# controller.net
KiCad netlist of a schematic drawn in EAGLE
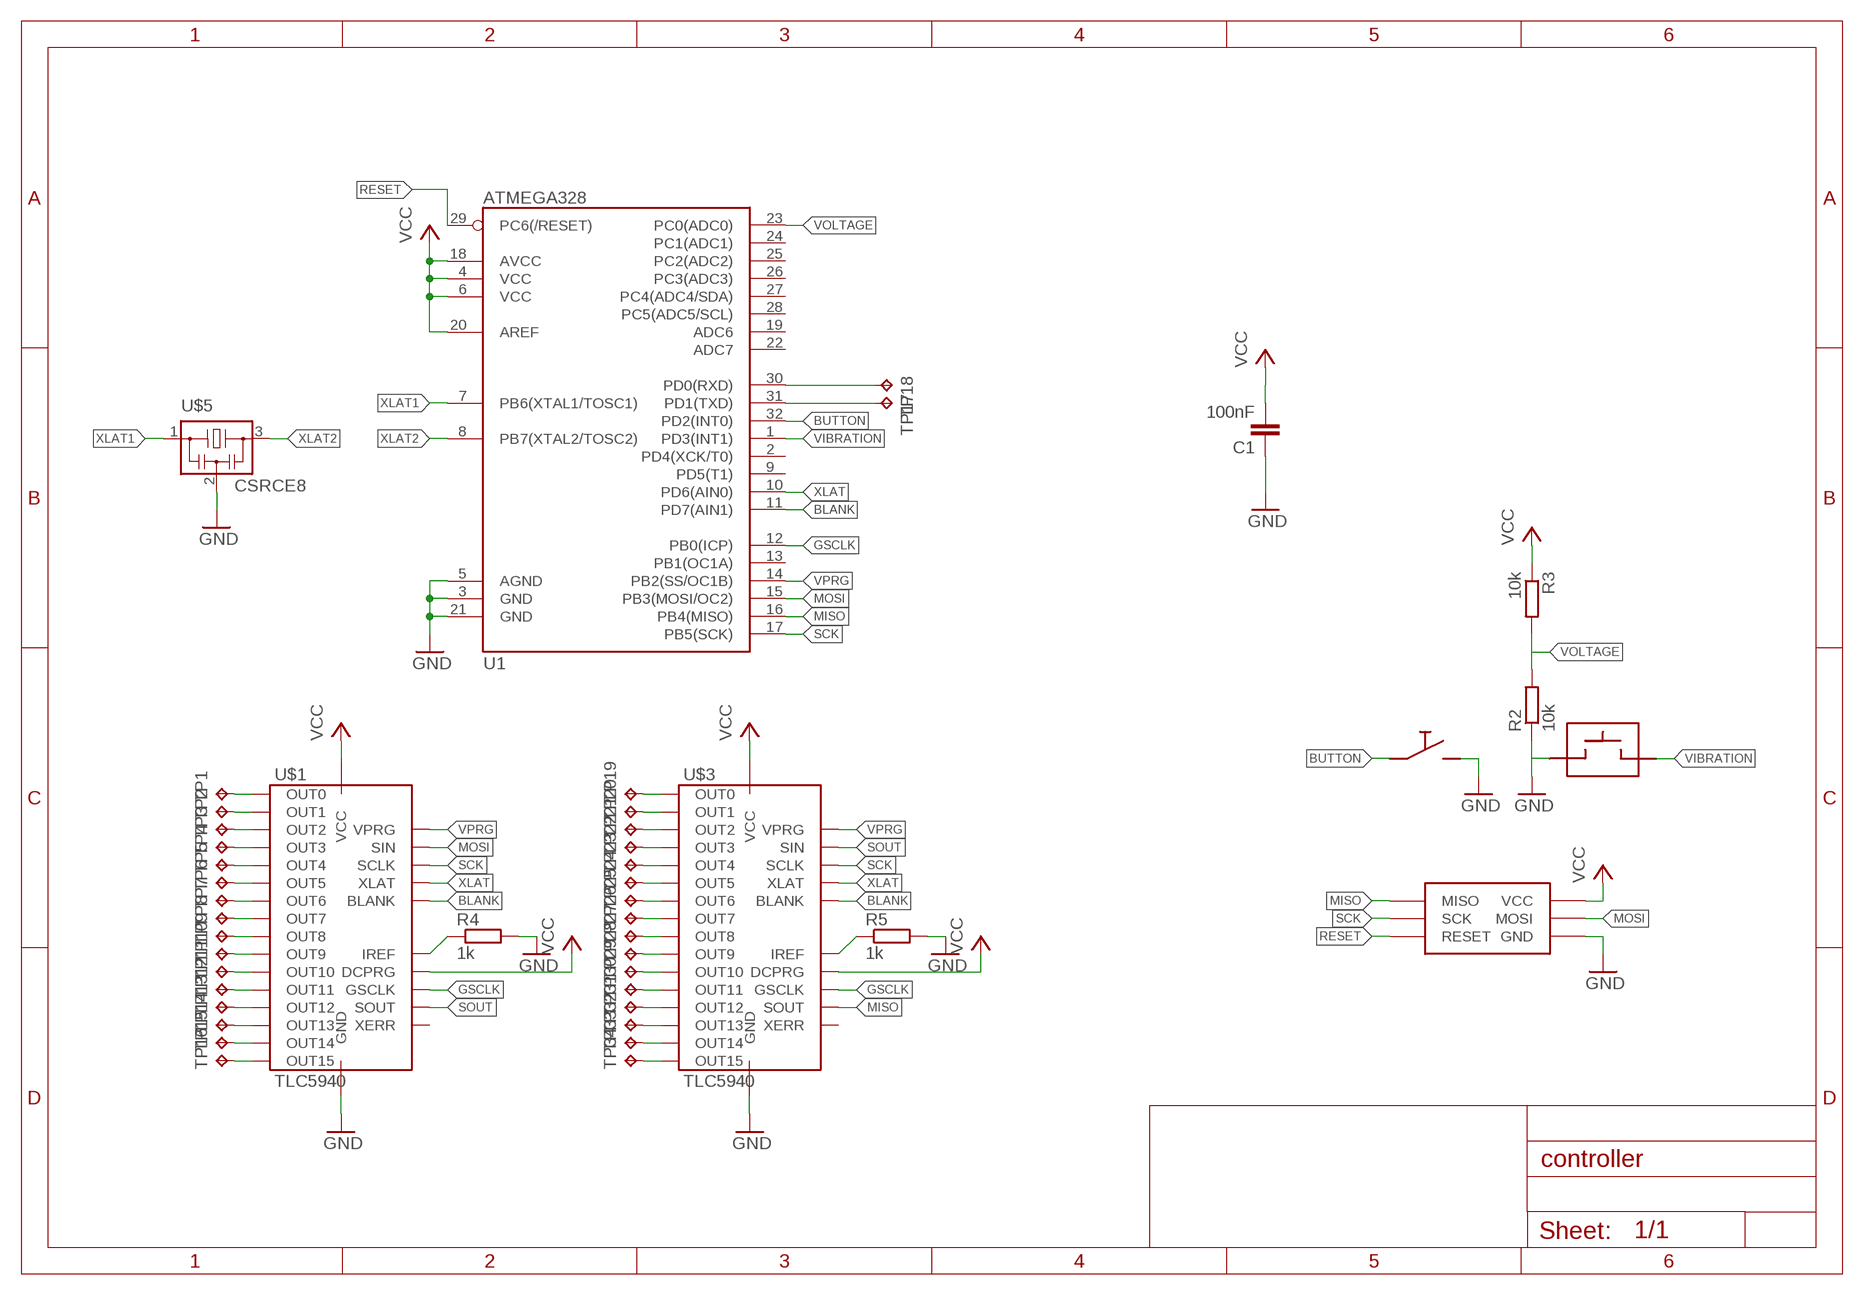
[diagram p0: schematic, sheet 1]

(export (version "E")
  (design (tool "Eeschema 10.0.6"))
  (components
    (comp (ref "C1")
      (value "100nF")
      (footprint "eagle-import:C0603")
      (libsource (lib "eagle-import") (part "C-EUC0603"))
    )
    (comp (ref "R2")
      (value "10k")
      (footprint "eagle-import:R0603")
      (libsource (lib "eagle-import") (part "R-EU_R0603"))
    )
    (comp (ref "R3")
      (value "10k")
      (footprint "eagle-import:R0603")
      (libsource (lib "eagle-import") (part "R-EU_R0603"))
    )
    (comp (ref "R4")
      (value "1k")
      (footprint "eagle-import:R0603")
      (libsource (lib "eagle-import") (part "R-EU_R0603"))
    )
    (comp (ref "R5")
      (value "1k")
      (footprint "eagle-import:R0603")
      (libsource (lib "eagle-import") (part "R-EU_R0603"))
    )
    (comp (ref "TP1")
      (value "TPTP15SQ")
      (footprint "eagle-import:TP15SQ")
      (libsource (lib "eagle-import") (part "TPTP15SQ"))
    )
    (comp (ref "TP2")
      (value "TPTP15SQ")
      (footprint "eagle-import:TP15SQ")
      (libsource (lib "eagle-import") (part "TPTP15SQ"))
    )
    (comp (ref "TP3")
      (value "TPTP15SQ")
      (footprint "eagle-import:TP15SQ")
      (libsource (lib "eagle-import") (part "TPTP15SQ"))
    )
    (comp (ref "TP4")
      (value "TPTP15SQ")
      (footprint "eagle-import:TP15SQ")
      (libsource (lib "eagle-import") (part "TPTP15SQ"))
    )
    (comp (ref "TP5")
      (value "TPTP15SQ")
      (footprint "eagle-import:TP15SQ")
      (libsource (lib "eagle-import") (part "TPTP15SQ"))
    )
    (comp (ref "TP6")
      (value "TPTP15SQ")
      (footprint "eagle-import:TP15SQ")
      (libsource (lib "eagle-import") (part "TPTP15SQ"))
    )
    (comp (ref "TP7")
      (value "TPTP15SQ")
      (footprint "eagle-import:TP15SQ")
      (libsource (lib "eagle-import") (part "TPTP15SQ"))
    )
    (comp (ref "TP8")
      (value "TPTP15SQ")
      (footprint "eagle-import:TP15SQ")
      (libsource (lib "eagle-import") (part "TPTP15SQ"))
    )
    (comp (ref "TP9")
      (value "TPTP15SQ")
      (footprint "eagle-import:TP15SQ")
      (libsource (lib "eagle-import") (part "TPTP15SQ"))
    )
    (comp (ref "TP10")
      (value "TPTP15SQ")
      (footprint "eagle-import:TP15SQ")
      (libsource (lib "eagle-import") (part "TPTP15SQ"))
    )
    (comp (ref "TP11")
      (value "TPTP15SQ")
      (footprint "eagle-import:TP15SQ")
      (libsource (lib "eagle-import") (part "TPTP15SQ"))
    )
    (comp (ref "TP12")
      (value "TPTP15SQ")
      (footprint "eagle-import:TP15SQ")
      (libsource (lib "eagle-import") (part "TPTP15SQ"))
    )
    (comp (ref "TP13")
      (value "TPTP15SQ")
      (footprint "eagle-import:TP15SQ")
      (libsource (lib "eagle-import") (part "TPTP15SQ"))
    )
    (comp (ref "TP14")
      (value "TPTP15SQ")
      (footprint "eagle-import:TP15SQ")
      (libsource (lib "eagle-import") (part "TPTP15SQ"))
    )
    (comp (ref "TP15")
      (value "TPTP15SQ")
      (footprint "eagle-import:TP15SQ")
      (libsource (lib "eagle-import") (part "TPTP15SQ"))
    )
    (comp (ref "TP16")
      (value "TPTP15SQ")
      (footprint "eagle-import:TP15SQ")
      (libsource (lib "eagle-import") (part "TPTP15SQ"))
    )
    (comp (ref "TP17")
      (value "TPTP15SQ")
      (footprint "eagle-import:TP15SQ")
      (libsource (lib "eagle-import") (part "TPTP15SQ"))
    )
    (comp (ref "TP18")
      (value "TPTP15SQ")
      (footprint "eagle-import:TP15SQ")
      (libsource (lib "eagle-import") (part "TPTP15SQ"))
    )
    (comp (ref "TP19")
      (value "TPTP15SQ")
      (footprint "eagle-import:TP15SQ")
      (libsource (lib "eagle-import") (part "TPTP15SQ"))
    )
    (comp (ref "TP20")
      (value "TPTP15SQ")
      (footprint "eagle-import:TP15SQ")
      (libsource (lib "eagle-import") (part "TPTP15SQ"))
    )
    (comp (ref "TP21")
      (value "TPTP15SQ")
      (footprint "eagle-import:TP15SQ")
      (libsource (lib "eagle-import") (part "TPTP15SQ"))
    )
    (comp (ref "TP22")
      (value "TPTP15SQ")
      (footprint "eagle-import:TP15SQ")
      (libsource (lib "eagle-import") (part "TPTP15SQ"))
    )
    (comp (ref "TP23")
      (value "TPTP15SQ")
      (footprint "eagle-import:TP15SQ")
      (libsource (lib "eagle-import") (part "TPTP15SQ"))
    )
    (comp (ref "TP24")
      (value "TPTP15SQ")
      (footprint "eagle-import:TP15SQ")
      (libsource (lib "eagle-import") (part "TPTP15SQ"))
    )
    (comp (ref "TP25")
      (value "TPTP15SQ")
      (footprint "eagle-import:TP15SQ")
      (libsource (lib "eagle-import") (part "TPTP15SQ"))
    )
    (comp (ref "TP26")
      (value "TPTP15SQ")
      (footprint "eagle-import:TP15SQ")
      (libsource (lib "eagle-import") (part "TPTP15SQ"))
    )
    (comp (ref "TP27")
      (value "TPTP15SQ")
      (footprint "eagle-import:TP15SQ")
      (libsource (lib "eagle-import") (part "TPTP15SQ"))
    )
    (comp (ref "TP28")
      (value "TPTP15SQ")
      (footprint "eagle-import:TP15SQ")
      (libsource (lib "eagle-import") (part "TPTP15SQ"))
    )
    (comp (ref "TP29")
      (value "TPTP15SQ")
      (footprint "eagle-import:TP15SQ")
      (libsource (lib "eagle-import") (part "TPTP15SQ"))
    )
    (comp (ref "TP30")
      (value "TPTP15SQ")
      (footprint "eagle-import:TP15SQ")
      (libsource (lib "eagle-import") (part "TPTP15SQ"))
    )
    (comp (ref "TP31")
      (value "TPTP15SQ")
      (footprint "eagle-import:TP15SQ")
      (libsource (lib "eagle-import") (part "TPTP15SQ"))
    )
    (comp (ref "TP32")
      (value "TPTP15SQ")
      (footprint "eagle-import:TP15SQ")
      (libsource (lib "eagle-import") (part "TPTP15SQ"))
    )
    (comp (ref "TP33")
      (value "TPTP15SQ")
      (footprint "eagle-import:TP15SQ")
      (libsource (lib "eagle-import") (part "TPTP15SQ"))
    )
    (comp (ref "TP34")
      (value "TPTP15SQ")
      (footprint "eagle-import:TP15SQ")
      (libsource (lib "eagle-import") (part "TPTP15SQ"))
    )
    (comp (ref "U$1")
      (value "TLC5940")
      (footprint "eagle-import:PWP_28PIN")
      (libsource (lib "eagle-import") (part "TLC5940"))
    )
    (comp (ref "U$2")
      (value "ISP_SPECIALS")
      (footprint "eagle-import:ISP_RM2_00_STRAIGHT")
      (libsource (lib "eagle-import") (part "ISP_SPECIALS"))
    )
    (comp (ref "U$3")
      (value "TLC5940")
      (footprint "eagle-import:PWP_28PIN")
      (libsource (lib "eagle-import") (part "TLC5940"))
    )
    (comp (ref "U$4")
      (value "MOTION_SENSOR")
      (footprint "eagle-import:MOTION")
      (libsource (lib "eagle-import") (part "MOTION_SENSOR"))
    )
    (comp (ref "U$5")
      (value "CSRCE8")
      (footprint "eagle-import:CSTCE_G")
      (libsource (lib "eagle-import") (part "CSRCE8"))
    )
    (comp (ref "U$6")
      (value "SWITCH")
      (footprint "eagle-import:EVQPSG02K")
      (libsource (lib "eagle-import") (part "SWITCH"))
    )
    (comp (ref "U1")
      (value "ATMEGA328")
      (footprint "eagle-import:TQFP32-08")
      (libsource (lib "eagle-import") (part "ATMEGA328"))
    )
  )
  (nets
    (net (code "1") (name "BLANK") (class "Default")
      (node (ref "U$1") (pin "P2") (pinfunction "BLANK_P2") (pintype "input"))
      (node (ref "U$3") (pin "P2") (pinfunction "BLANK_P2") (pintype "input"))
      (node (ref "U1") (pin "11") (pinfunction "PD7(AIN1)_11") (pintype "bidirectional"))
    )
    (net (code "2") (name "BUTTON") (class "Default")
      (node (ref "U$6") (pin "A") (pinfunction "P$1_A") (pintype "bidirectional"))
      (node (ref "U$6") (pin "A@2") (pinfunction "P$1_A@2") (pintype "bidirectional"))
      (node (ref "U1") (pin "32") (pinfunction "PD2(INT0)_32") (pintype "bidirectional"))
    )
    (net (code "3") (name "GND") (class "Default")
      (node (ref "C1") (pin "1") (pinfunction "1_1") (pintype "passive"))
      (node (ref "R2") (pin "1") (pinfunction "1_1") (pintype "passive"))
      (node (ref "R4") (pin "2") (pinfunction "2_2") (pintype "passive"))
      (node (ref "R5") (pin "2") (pinfunction "2_2") (pintype "passive"))
      (node (ref "U$1") (pin "P1") (pinfunction "GND_P1") (pintype "power_in"))
      (node (ref "U$1") (pin "P29") (pinfunction "GND_P29") (pintype "power_in"))
      (node (ref "U$2") (pin "VCC") (pinfunction "GND_VCC") (pintype "bidirectional"))
      (node (ref "U$3") (pin "P1") (pinfunction "GND_P1") (pintype "power_in"))
      (node (ref "U$3") (pin "P29") (pinfunction "GND_P29") (pintype "power_in"))
      (node (ref "U$4") (pin "P$1") (pinfunction "IN_P$1") (pintype "bidirectional"))
      (node (ref "U$5") (pin "2") (pinfunction "2_2") (pintype "passive"))
      (node (ref "U$6") (pin "B") (pinfunction "P$2_B") (pintype "bidirectional"))
      (node (ref "U$6") (pin "B@2") (pinfunction "P$2_B@2") (pintype "bidirectional"))
      (node (ref "U1") (pin "21") (pinfunction "GND_21") (pintype "bidirectional"))
      (node (ref "U1") (pin "3") (pinfunction "GND_3") (pintype "bidirectional"))
      (node (ref "U1") (pin "5") (pinfunction "AGND_5") (pintype "bidirectional"))
    )
    (net (code "4") (name "GSCLK") (class "Default")
      (node (ref "U$1") (pin "P25") (pinfunction "GSCLK_P25") (pintype "input"))
      (node (ref "U$3") (pin "P25") (pinfunction "GSCLK_P25") (pintype "input"))
      (node (ref "U1") (pin "12") (pinfunction "PB0(ICP)_12") (pintype "bidirectional"))
    )
    (net (code "5") (name "MISO") (class "Default")
      (node (ref "U$2") (pin "RESET") (pinfunction "MISO_RESET") (pintype "bidirectional"))
      (node (ref "U$3") (pin "P24") (pinfunction "SOUT_P24") (pintype "output"))
      (node (ref "U1") (pin "16") (pinfunction "PB4(MISO)_16") (pintype "bidirectional"))
    )
    (net (code "6") (name "MOSI") (class "Default")
      (node (ref "U$1") (pin "P5") (pinfunction "SIN_P5") (pintype "input"))
      (node (ref "U$2") (pin "MOSI") (pinfunction "MOSI_MOSI") (pintype "bidirectional"))
      (node (ref "U1") (pin "15") (pinfunction "PB3(MOSI/OC2)_15") (pintype "bidirectional"))
    )
    (net (code "7") (name "Net-(U$1-IREF)") (class "Default")
      (node (ref "R4") (pin "1") (pinfunction "1_1") (pintype "passive"))
      (node (ref "U$1") (pin "P27") (pinfunction "IREF_P27") (pintype "passive"))
    )
    (net (code "8") (name "Net-(U$1-OUT0)") (class "Default")
      (node (ref "TP1") (pin "TP") (pinfunction "TP_TP") (pintype "input"))
      (node (ref "U$1") (pin "P7") (pinfunction "OUT0_P7") (pintype "open_collector"))
    )
    (net (code "9") (name "Net-(U$1-OUT1)") (class "Default")
      (node (ref "TP2") (pin "TP") (pinfunction "TP_TP") (pintype "input"))
      (node (ref "U$1") (pin "P8") (pinfunction "OUT1_P8") (pintype "open_collector"))
    )
    (net (code "10") (name "Net-(U$1-OUT2)") (class "Default")
      (node (ref "TP3") (pin "TP") (pinfunction "TP_TP") (pintype "input"))
      (node (ref "U$1") (pin "P9") (pinfunction "OUT2_P9") (pintype "open_collector"))
    )
    (net (code "11") (name "Net-(U$1-OUT3)") (class "Default")
      (node (ref "TP4") (pin "TP") (pinfunction "TP_TP") (pintype "input"))
      (node (ref "U$1") (pin "P10") (pinfunction "OUT3_P10") (pintype "open_collector"))
    )
    (net (code "12") (name "Net-(U$1-OUT4)") (class "Default")
      (node (ref "TP5") (pin "TP") (pinfunction "TP_TP") (pintype "input"))
      (node (ref "U$1") (pin "P11") (pinfunction "OUT4_P11") (pintype "open_collector"))
    )
    (net (code "13") (name "Net-(U$1-OUT5)") (class "Default")
      (node (ref "TP6") (pin "TP") (pinfunction "TP_TP") (pintype "input"))
      (node (ref "U$1") (pin "P12") (pinfunction "OUT5_P12") (pintype "open_collector"))
    )
    (net (code "14") (name "Net-(U$1-OUT6)") (class "Default")
      (node (ref "TP7") (pin "TP") (pinfunction "TP_TP") (pintype "input"))
      (node (ref "U$1") (pin "P13") (pinfunction "OUT6_P13") (pintype "open_collector"))
    )
    (net (code "15") (name "Net-(U$1-OUT7)") (class "Default")
      (node (ref "TP8") (pin "TP") (pinfunction "TP_TP") (pintype "input"))
      (node (ref "U$1") (pin "P14") (pinfunction "OUT7_P14") (pintype "open_collector"))
    )
    (net (code "16") (name "Net-(U$1-OUT8)") (class "Default")
      (node (ref "TP9") (pin "TP") (pinfunction "TP_TP") (pintype "input"))
      (node (ref "U$1") (pin "P15") (pinfunction "OUT8_P15") (pintype "open_collector"))
    )
    (net (code "17") (name "Net-(U$1-OUT9)") (class "Default")
      (node (ref "TP10") (pin "TP") (pinfunction "TP_TP") (pintype "input"))
      (node (ref "U$1") (pin "P16") (pinfunction "OUT9_P16") (pintype "open_collector"))
    )
    (net (code "18") (name "Net-(U$1-OUT10)") (class "Default")
      (node (ref "TP11") (pin "TP") (pinfunction "TP_TP") (pintype "input"))
      (node (ref "U$1") (pin "P17") (pinfunction "OUT10_P17") (pintype "open_collector"))
    )
    (net (code "19") (name "Net-(U$1-OUT11)") (class "Default")
      (node (ref "TP12") (pin "TP") (pinfunction "TP_TP") (pintype "input"))
      (node (ref "U$1") (pin "P18") (pinfunction "OUT11_P18") (pintype "open_collector"))
    )
    (net (code "20") (name "Net-(U$1-OUT12)") (class "Default")
      (node (ref "TP13") (pin "TP") (pinfunction "TP_TP") (pintype "input"))
      (node (ref "U$1") (pin "P19") (pinfunction "OUT12_P19") (pintype "open_collector"))
    )
    (net (code "21") (name "Net-(U$1-OUT13)") (class "Default")
      (node (ref "TP14") (pin "TP") (pinfunction "TP_TP") (pintype "input"))
      (node (ref "U$1") (pin "P20") (pinfunction "OUT13_P20") (pintype "open_collector"))
    )
    (net (code "22") (name "Net-(U$1-OUT14)") (class "Default")
      (node (ref "TP15") (pin "TP") (pinfunction "TP_TP") (pintype "input"))
      (node (ref "U$1") (pin "P21") (pinfunction "OUT14_P21") (pintype "open_collector"))
    )
    (net (code "23") (name "Net-(U$1-OUT15)") (class "Default")
      (node (ref "TP16") (pin "TP") (pinfunction "TP_TP") (pintype "input"))
      (node (ref "U$1") (pin "P22") (pinfunction "OUT15_P22") (pintype "open_collector"))
    )
    (net (code "24") (name "Net-(U$3-IREF)") (class "Default")
      (node (ref "R5") (pin "1") (pinfunction "1_1") (pintype "passive"))
      (node (ref "U$3") (pin "P27") (pinfunction "IREF_P27") (pintype "passive"))
    )
    (net (code "25") (name "Net-(U$3-OUT0)") (class "Default")
      (node (ref "TP19") (pin "TP") (pinfunction "TP_TP") (pintype "input"))
      (node (ref "U$3") (pin "P7") (pinfunction "OUT0_P7") (pintype "open_collector"))
    )
    (net (code "26") (name "Net-(U$3-OUT1)") (class "Default")
      (node (ref "TP20") (pin "TP") (pinfunction "TP_TP") (pintype "input"))
      (node (ref "U$3") (pin "P8") (pinfunction "OUT1_P8") (pintype "open_collector"))
    )
    (net (code "27") (name "Net-(U$3-OUT2)") (class "Default")
      (node (ref "TP21") (pin "TP") (pinfunction "TP_TP") (pintype "input"))
      (node (ref "U$3") (pin "P9") (pinfunction "OUT2_P9") (pintype "open_collector"))
    )
    (net (code "28") (name "Net-(U$3-OUT3)") (class "Default")
      (node (ref "TP22") (pin "TP") (pinfunction "TP_TP") (pintype "input"))
      (node (ref "U$3") (pin "P10") (pinfunction "OUT3_P10") (pintype "open_collector"))
    )
    (net (code "29") (name "Net-(U$3-OUT4)") (class "Default")
      (node (ref "TP23") (pin "TP") (pinfunction "TP_TP") (pintype "input"))
      (node (ref "U$3") (pin "P11") (pinfunction "OUT4_P11") (pintype "open_collector"))
    )
    (net (code "30") (name "Net-(U$3-OUT5)") (class "Default")
      (node (ref "TP24") (pin "TP") (pinfunction "TP_TP") (pintype "input"))
      (node (ref "U$3") (pin "P12") (pinfunction "OUT5_P12") (pintype "open_collector"))
    )
    (net (code "31") (name "Net-(U$3-OUT6)") (class "Default")
      (node (ref "TP25") (pin "TP") (pinfunction "TP_TP") (pintype "input"))
      (node (ref "U$3") (pin "P13") (pinfunction "OUT6_P13") (pintype "open_collector"))
    )
    (net (code "32") (name "Net-(U$3-OUT7)") (class "Default")
      (node (ref "TP26") (pin "TP") (pinfunction "TP_TP") (pintype "input"))
      (node (ref "U$3") (pin "P14") (pinfunction "OUT7_P14") (pintype "open_collector"))
    )
    (net (code "33") (name "Net-(U$3-OUT8)") (class "Default")
      (node (ref "TP27") (pin "TP") (pinfunction "TP_TP") (pintype "input"))
      (node (ref "U$3") (pin "P15") (pinfunction "OUT8_P15") (pintype "open_collector"))
    )
    (net (code "34") (name "Net-(U$3-OUT9)") (class "Default")
      (node (ref "TP28") (pin "TP") (pinfunction "TP_TP") (pintype "input"))
      (node (ref "U$3") (pin "P16") (pinfunction "OUT9_P16") (pintype "open_collector"))
    )
    (net (code "35") (name "Net-(U$3-OUT10)") (class "Default")
      (node (ref "TP29") (pin "TP") (pinfunction "TP_TP") (pintype "input"))
      (node (ref "U$3") (pin "P17") (pinfunction "OUT10_P17") (pintype "open_collector"))
    )
    (net (code "36") (name "Net-(U$3-OUT11)") (class "Default")
      (node (ref "TP30") (pin "TP") (pinfunction "TP_TP") (pintype "input"))
      (node (ref "U$3") (pin "P18") (pinfunction "OUT11_P18") (pintype "open_collector"))
    )
    (net (code "37") (name "Net-(U$3-OUT12)") (class "Default")
      (node (ref "TP31") (pin "TP") (pinfunction "TP_TP") (pintype "input"))
      (node (ref "U$3") (pin "P19") (pinfunction "OUT12_P19") (pintype "open_collector"))
    )
    (net (code "38") (name "Net-(U$3-OUT13)") (class "Default")
      (node (ref "TP32") (pin "TP") (pinfunction "TP_TP") (pintype "input"))
      (node (ref "U$3") (pin "P20") (pinfunction "OUT13_P20") (pintype "open_collector"))
    )
    (net (code "39") (name "Net-(U$3-OUT14)") (class "Default")
      (node (ref "TP33") (pin "TP") (pinfunction "TP_TP") (pintype "input"))
      (node (ref "U$3") (pin "P21") (pinfunction "OUT14_P21") (pintype "open_collector"))
    )
    (net (code "40") (name "Net-(U$3-OUT15)") (class "Default")
      (node (ref "TP34") (pin "TP") (pinfunction "TP_TP") (pintype "input"))
      (node (ref "U$3") (pin "P22") (pinfunction "OUT15_P22") (pintype "open_collector"))
    )
    (net (code "41") (name "Net-(U1-PD0(RXD))") (class "Default")
      (node (ref "TP18") (pin "TP") (pinfunction "TP_TP") (pintype "input"))
      (node (ref "U1") (pin "30") (pinfunction "PD0(RXD)_30") (pintype "bidirectional"))
    )
    (net (code "42") (name "Net-(U1-PD1(TXD))") (class "Default")
      (node (ref "TP17") (pin "TP") (pinfunction "TP_TP") (pintype "input"))
      (node (ref "U1") (pin "31") (pinfunction "PD1(TXD)_31") (pintype "bidirectional"))
    )
    (net (code "43") (name "RESET") (class "Default")
      (node (ref "U$2") (pin "MISO") (pinfunction "RESET_MISO") (pintype "bidirectional"))
      (node (ref "U1") (pin "29") (pinfunction "PC6(/RESET)_29") (pintype "bidirectional"))
    )
    (net (code "44") (name "SCK") (class "Default")
      (node (ref "U$1") (pin "P4") (pinfunction "SCLK_P4") (pintype "input"))
      (node (ref "U$2") (pin "SCK") (pinfunction "SCK_SCK") (pintype "bidirectional"))
      (node (ref "U$3") (pin "P4") (pinfunction "SCLK_P4") (pintype "input"))
      (node (ref "U1") (pin "17") (pinfunction "PB5(SCK)_17") (pintype "bidirectional"))
    )
    (net (code "45") (name "SOUT") (class "Default")
      (node (ref "U$1") (pin "P24") (pinfunction "SOUT_P24") (pintype "output"))
      (node (ref "U$3") (pin "P5") (pinfunction "SIN_P5") (pintype "input"))
    )
    (net (code "46") (name "VCC") (class "Default")
      (node (ref "C1") (pin "2") (pinfunction "2_2") (pintype "passive"))
      (node (ref "R3") (pin "1") (pinfunction "1_1") (pintype "passive"))
      (node (ref "U$1") (pin "P26") (pinfunction "DCPRG_P26") (pintype "input"))
      (node (ref "U$1") (pin "P28") (pinfunction "VCC_P28") (pintype "power_in"))
      (node (ref "U$2") (pin "GND") (pinfunction "VCC_GND") (pintype "bidirectional"))
      (node (ref "U$3") (pin "P26") (pinfunction "DCPRG_P26") (pintype "input"))
      (node (ref "U$3") (pin "P28") (pinfunction "VCC_P28") (pintype "power_in"))
      (node (ref "U1") (pin "18") (pinfunction "AVCC_18") (pintype "bidirectional"))
      (node (ref "U1") (pin "20") (pinfunction "AREF_20") (pintype "bidirectional"))
      (node (ref "U1") (pin "4") (pinfunction "VCC_4") (pintype "bidirectional"))
      (node (ref "U1") (pin "6") (pinfunction "VCC_6") (pintype "bidirectional"))
    )
    (net (code "47") (name "VIBRATION") (class "Default")
      (node (ref "U$4") (pin "P$2") (pinfunction "OUT_P$2") (pintype "bidirectional"))
      (node (ref "U1") (pin "1") (pinfunction "PD3(INT1)_1") (pintype "bidirectional"))
    )
    (net (code "48") (name "VOLTAGE") (class "Default")
      (node (ref "R2") (pin "2") (pinfunction "2_2") (pintype "passive"))
      (node (ref "R3") (pin "2") (pinfunction "2_2") (pintype "passive"))
      (node (ref "U1") (pin "23") (pinfunction "PC0(ADC0)_23") (pintype "bidirectional"))
    )
    (net (code "49") (name "VPRG") (class "Default")
      (node (ref "U$1") (pin "P6") (pinfunction "VPRG_P6") (pintype "input"))
      (node (ref "U$3") (pin "P6") (pinfunction "VPRG_P6") (pintype "input"))
      (node (ref "U1") (pin "14") (pinfunction "PB2(SS/OC1B)_14") (pintype "bidirectional"))
    )
    (net (code "50") (name "XLAT") (class "Default")
      (node (ref "U$1") (pin "P3") (pinfunction "XLAT_P3") (pintype "input"))
      (node (ref "U$3") (pin "P3") (pinfunction "XLAT_P3") (pintype "input"))
      (node (ref "U1") (pin "10") (pinfunction "PD6(AIN0)_10") (pintype "bidirectional"))
    )
    (net (code "51") (name "XLAT1") (class "Default")
      (node (ref "U$5") (pin "1") (pinfunction "1_1") (pintype "passive"))
      (node (ref "U1") (pin "7") (pinfunction "PB6(XTAL1/TOSC1)_7") (pintype "bidirectional"))
    )
    (net (code "52") (name "XLAT2") (class "Default")
      (node (ref "U$5") (pin "3") (pinfunction "3_3") (pintype "passive"))
      (node (ref "U1") (pin "8") (pinfunction "PB7(XTAL2/TOSC2)_8") (pintype "bidirectional"))
    )
    (net (code "53") (name "unconnected-(U$1-XERR-PadP23)") (class "Default")
      (node (ref "U$1") (pin "P23") (pinfunction "XERR_P23") (pintype "open_collector"))
    )
    (net (code "54") (name "unconnected-(U$3-XERR-PadP23)") (class "Default")
      (node (ref "U$3") (pin "P23") (pinfunction "XERR_P23") (pintype "open_collector"))
    )
    (net (code "55") (name "unconnected-(U1-ADC6-Pad19)") (class "Default")
      (node (ref "U1") (pin "19") (pinfunction "ADC6_19") (pintype "bidirectional"))
    )
    (net (code "56") (name "unconnected-(U1-ADC7-Pad22)") (class "Default")
      (node (ref "U1") (pin "22") (pinfunction "ADC7_22") (pintype "bidirectional"))
    )
    (net (code "57") (name "unconnected-(U1-PB1(OC1A)-Pad13)") (class "Default")
      (node (ref "U1") (pin "13") (pinfunction "PB1(OC1A)_13") (pintype "bidirectional"))
    )
    (net (code "58") (name "unconnected-(U1-PC1(ADC1)-Pad24)") (class "Default")
      (node (ref "U1") (pin "24") (pinfunction "PC1(ADC1)_24") (pintype "bidirectional"))
    )
    (net (code "59") (name "unconnected-(U1-PC2(ADC2)-Pad25)") (class "Default")
      (node (ref "U1") (pin "25") (pinfunction "PC2(ADC2)_25") (pintype "bidirectional"))
    )
    (net (code "60") (name "unconnected-(U1-PC3(ADC3)-Pad26)") (class "Default")
      (node (ref "U1") (pin "26") (pinfunction "PC3(ADC3)_26") (pintype "bidirectional"))
    )
    (net (code "61") (name "unconnected-(U1-PC4(ADC4{slash}SDA)-Pad27)") (class "Default")
      (node (ref "U1") (pin "27") (pinfunction "PC4(ADC4/SDA)_27") (pintype "bidirectional"))
    )
    (net (code "62") (name "unconnected-(U1-PC5(ADC5{slash}SCL)-Pad28)") (class "Default")
      (node (ref "U1") (pin "28") (pinfunction "PC5(ADC5/SCL)_28") (pintype "bidirectional"))
    )
    (net (code "63") (name "unconnected-(U1-PD4(XCK{slash}T0)-Pad2)") (class "Default")
      (node (ref "U1") (pin "2") (pinfunction "PD4(XCK/T0)_2") (pintype "bidirectional"))
    )
    (net (code "64") (name "unconnected-(U1-PD5(T1)-Pad9)") (class "Default")
      (node (ref "U1") (pin "9") (pinfunction "PD5(T1)_9") (pintype "bidirectional"))
    )
  )
)
